# PATHOS_PowerSupply.net
KiCad netlist of a schematic drawn in Altium Designer
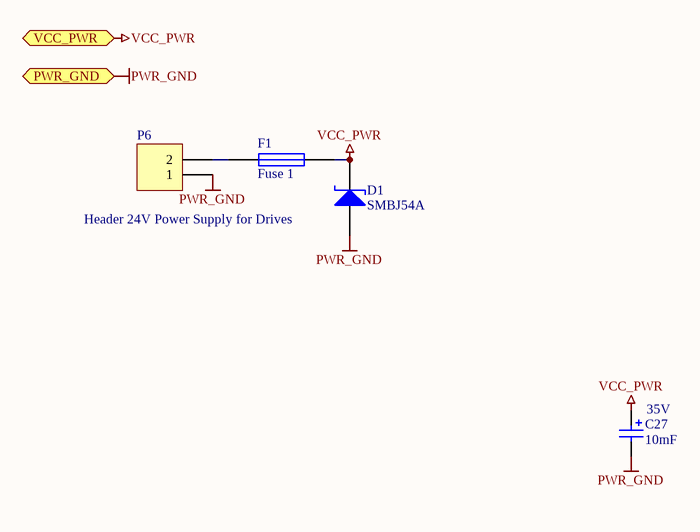
[diagram p0: PATHOS_PowerSupply.SchDoc]

(export (version "E")
  (design (tool "Eeschema 10.0.6"))
  (components
    (comp (ref "C27")
      (value "10mF")
      (footprint "Cap_SLP_C7_10mF")
      (description "Polarized Capacitor Positive Mark Bar")
      (fields (field (name "VOLTAGE MAXIUM") "35V") (field (name "#PUBLISHER") "Dr. A. Heinzelmann"))
      (libsource (lib "ELE-LIB") (part "C_POL"))
    )
    (comp (ref "D1")
      (value "SMBJ54A")
      (footprint "TVS_DO214AA")
      (description "TVS Diode")
      (fields (field (name "PUBLISHER") "Altium Limited"))
      (libsource (lib "Pathos_Div") (part "Diode SMBJ54A"))
    )
    (comp (ref "F1")
      (value "Fuse 1")
      (footprint "Fuse40ASMD")
      (description "Fuse")
      (fields (field (name "PUBLISHER") "Altium Limited"))
      (libsource (lib "Miscellaneous Devices") (part "Fuse 1"))
    )
    (comp (ref "P6")
      (value "Header 24V Power Supply for Drives")
      (footprint "PhoenixHeader5_08_Vertical_unsymetric")
      (description "Header, 2-Pin")
      (fields (field (name "PUBLISHER") "Altium Limited"))
      (libsource (lib "Miscellaneous Connectors") (part "Header 2"))
    )
  )
  (nets
    (net (code "1") (name "Net-(F1-Pad1)") (class "Default")
      (node (ref "F1") (pin "1") (pinfunction "1_1") (pintype "passive"))
      (node (ref "P6") (pin "2") (pinfunction "2_2") (pintype "passive"))
    )
    (net (code "2") (name "PWR_GND") (class "Default")
      (node (ref "C27") (pin "2") (pinfunction "Neg_2") (pintype "passive"))
      (node (ref "D1") (pin "A") (pinfunction "A_A") (pintype "passive"))
      (node (ref "P6") (pin "1") (pinfunction "1_1") (pintype "passive"))
    )
    (net (code "3") (name "VCC_PWR") (class "Default")
      (node (ref "C27") (pin "1") (pinfunction "Pos_1") (pintype "passive"))
      (node (ref "D1") (pin "K") (pinfunction "K_K") (pintype "passive"))
      (node (ref "F1") (pin "2") (pinfunction "2_2") (pintype "passive"))
    )
  )
)
